# sensor.net
KiCad netlist of a schematic drawn in EAGLE
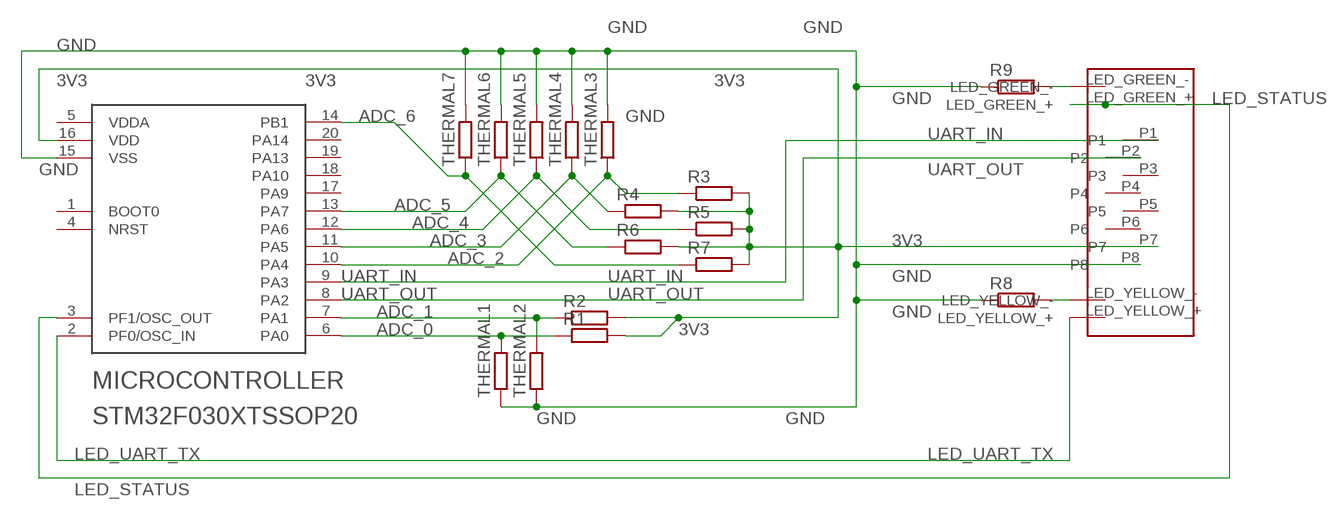
[diagram p0: schematic, sheet 1]

(export (version "E")
  (design (tool "Eeschema 10.0.6"))
  (components
    (comp (ref "MICROCONTROLLER")
      (value "STM32F030XTSSOP20")
      (footprint "eagle-import:TSSOP-20")
      (libsource (lib "eagle-import") (part "STM32F030XTSSOP20"))
    )
    (comp (ref "R1")
      (value "R-EU_0204/5")
      (footprint "eagle-import:0204_5")
      (libsource (lib "eagle-import") (part "R-EU_0204/5"))
    )
    (comp (ref "R2")
      (value "R-EU_0204/5")
      (footprint "eagle-import:0204_5")
      (libsource (lib "eagle-import") (part "R-EU_0204/5"))
    )
    (comp (ref "R3")
      (value "R-EU_0204/5")
      (footprint "eagle-import:0204_5")
      (libsource (lib "eagle-import") (part "R-EU_0204/5"))
    )
    (comp (ref "R4")
      (value "R-EU_0204/5")
      (footprint "eagle-import:0204_5")
      (libsource (lib "eagle-import") (part "R-EU_0204/5"))
    )
    (comp (ref "R5")
      (value "R-EU_0204/5")
      (footprint "eagle-import:0204_5")
      (libsource (lib "eagle-import") (part "R-EU_0204/5"))
    )
    (comp (ref "R6")
      (value "R-EU_0204/5")
      (footprint "eagle-import:0204_5")
      (libsource (lib "eagle-import") (part "R-EU_0204/5"))
    )
    (comp (ref "R7")
      (value "R-EU_0204/5")
      (footprint "eagle-import:0204_5")
      (libsource (lib "eagle-import") (part "R-EU_0204/5"))
    )
    (comp (ref "R8")
      (value "R-EU_0204/5")
      (footprint "eagle-import:0204_5")
      (libsource (lib "eagle-import") (part "R-EU_0204/5"))
    )
    (comp (ref "R9")
      (value "R-EU_0204/5")
      (footprint "eagle-import:0204_5")
      (libsource (lib "eagle-import") (part "R-EU_0204/5"))
    )
    (comp (ref "THERMAL1")
      (value "R-EU_V526-0")
      (footprint "eagle-import:V526-0")
      (libsource (lib "eagle-import") (part "R-EU_V526-0"))
    )
    (comp (ref "THERMAL2")
      (value "R-EU_V526-0")
      (footprint "eagle-import:V526-0")
      (libsource (lib "eagle-import") (part "R-EU_V526-0"))
    )
    (comp (ref "THERMAL3")
      (value "R-EU_V526-0")
      (footprint "eagle-import:V526-0")
      (libsource (lib "eagle-import") (part "R-EU_V526-0"))
    )
    (comp (ref "THERMAL4")
      (value "R-EU_V526-0")
      (footprint "eagle-import:V526-0")
      (libsource (lib "eagle-import") (part "R-EU_V526-0"))
    )
    (comp (ref "THERMAL5")
      (value "R-EU_V526-0")
      (footprint "eagle-import:V526-0")
      (libsource (lib "eagle-import") (part "R-EU_V526-0"))
    )
    (comp (ref "THERMAL6")
      (value "R-EU_V526-0")
      (footprint "eagle-import:V526-0")
      (libsource (lib "eagle-import") (part "R-EU_V526-0"))
    )
    (comp (ref "THERMAL7")
      (value "R-EU_V526-0")
      (footprint "eagle-import:V526-0")
      (libsource (lib "eagle-import") (part "R-EU_V526-0"))
    )
    (comp (ref "U$1")
      (value "RJHSE-5481_(RJ45)")
      (footprint "eagle-import:RJHSE-5481_(RJ45)")
      (libsource (lib "eagle-import") (part "RJHSE-5481_(RJ45)"))
    )
  )
  (nets
    (net (code "1") (name "/3V3") (class "Default")
      (node (ref "MICROCONTROLLER") (pin "16") (pinfunction "VDD_16") (pintype "bidirectional"))
      (node (ref "R1") (pin "2") (pinfunction "2_2") (pintype "passive"))
      (node (ref "R2") (pin "2") (pinfunction "2_2") (pintype "passive"))
      (node (ref "R3") (pin "2") (pinfunction "2_2") (pintype "passive"))
      (node (ref "R4") (pin "2") (pinfunction "2_2") (pintype "passive"))
      (node (ref "R5") (pin "2") (pinfunction "2_2") (pintype "passive"))
      (node (ref "R6") (pin "2") (pinfunction "2_2") (pintype "passive"))
      (node (ref "R7") (pin "2") (pinfunction "2_2") (pintype "passive"))
      (node (ref "U$1") (pin "P7") (pinfunction "P7_P7") (pintype "bidirectional"))
    )
    (net (code "2") (name "/ADC_0") (class "Default")
      (node (ref "MICROCONTROLLER") (pin "6") (pinfunction "PA0_6") (pintype "bidirectional"))
      (node (ref "R1") (pin "1") (pinfunction "1_1") (pintype "passive"))
      (node (ref "THERMAL1") (pin "2") (pinfunction "2_2") (pintype "passive"))
    )
    (net (code "3") (name "/ADC_1") (class "Default")
      (node (ref "MICROCONTROLLER") (pin "7") (pinfunction "PA1_7") (pintype "bidirectional"))
      (node (ref "R2") (pin "1") (pinfunction "1_1") (pintype "passive"))
      (node (ref "THERMAL2") (pin "2") (pinfunction "2_2") (pintype "passive"))
    )
    (net (code "4") (name "/ADC_2") (class "Default")
      (node (ref "MICROCONTROLLER") (pin "10") (pinfunction "PA4_10") (pintype "bidirectional"))
      (node (ref "R3") (pin "1") (pinfunction "1_1") (pintype "passive"))
      (node (ref "THERMAL3") (pin "1") (pinfunction "1_1") (pintype "passive"))
    )
    (net (code "5") (name "/ADC_3") (class "Default")
      (node (ref "MICROCONTROLLER") (pin "11") (pinfunction "PA5_11") (pintype "bidirectional"))
      (node (ref "R4") (pin "1") (pinfunction "1_1") (pintype "passive"))
      (node (ref "THERMAL4") (pin "1") (pinfunction "1_1") (pintype "passive"))
    )
    (net (code "6") (name "/ADC_4") (class "Default")
      (node (ref "MICROCONTROLLER") (pin "12") (pinfunction "PA6_12") (pintype "bidirectional"))
      (node (ref "R5") (pin "1") (pinfunction "1_1") (pintype "passive"))
      (node (ref "THERMAL5") (pin "1") (pinfunction "1_1") (pintype "passive"))
    )
    (net (code "7") (name "/ADC_5") (class "Default")
      (node (ref "MICROCONTROLLER") (pin "13") (pinfunction "PA7_13") (pintype "bidirectional"))
      (node (ref "R6") (pin "1") (pinfunction "1_1") (pintype "passive"))
      (node (ref "THERMAL6") (pin "1") (pinfunction "1_1") (pintype "passive"))
    )
    (net (code "8") (name "/ADC_6") (class "Default")
      (node (ref "MICROCONTROLLER") (pin "14") (pinfunction "PB1_14") (pintype "bidirectional"))
      (node (ref "R7") (pin "1") (pinfunction "1_1") (pintype "passive"))
      (node (ref "THERMAL7") (pin "1") (pinfunction "1_1") (pintype "passive"))
    )
    (net (code "9") (name "/GND") (class "Default")
      (node (ref "MICROCONTROLLER") (pin "15") (pinfunction "VSS_15") (pintype "bidirectional"))
      (node (ref "R8") (pin "1") (pinfunction "1_1") (pintype "passive"))
      (node (ref "R9") (pin "1") (pinfunction "1_1") (pintype "passive"))
      (node (ref "THERMAL1") (pin "1") (pinfunction "1_1") (pintype "passive"))
      (node (ref "THERMAL2") (pin "1") (pinfunction "1_1") (pintype "passive"))
      (node (ref "THERMAL3") (pin "2") (pinfunction "2_2") (pintype "passive"))
      (node (ref "THERMAL4") (pin "2") (pinfunction "2_2") (pintype "passive"))
      (node (ref "THERMAL5") (pin "2") (pinfunction "2_2") (pintype "passive"))
      (node (ref "THERMAL6") (pin "2") (pinfunction "2_2") (pintype "passive"))
      (node (ref "THERMAL7") (pin "2") (pinfunction "2_2") (pintype "passive"))
      (node (ref "U$1") (pin "P8") (pinfunction "P8_P8") (pintype "bidirectional"))
    )
    (net (code "10") (name "/LED_STATUS") (class "Default")
      (node (ref "MICROCONTROLLER") (pin "3") (pinfunction "PF1/OSC_OUT_3") (pintype "bidirectional"))
      (node (ref "U$1") (pin "LED_GREEN_+") (pinfunction "LED_GREEN_+_LED_GREEN_+") (pintype "input"))
    )
    (net (code "11") (name "/LED_UART_TX") (class "Default")
      (node (ref "MICROCONTROLLER") (pin "2") (pinfunction "PF0/OSC_IN_2") (pintype "bidirectional"))
    )
    (net (code "12") (name "/UART_IN") (class "Default")
      (node (ref "MICROCONTROLLER") (pin "9") (pinfunction "PA3_9") (pintype "bidirectional"))
      (node (ref "U$1") (pin "P1") (pinfunction "P1_P1") (pintype "bidirectional"))
    )
    (net (code "13") (name "/UART_OUT") (class "Default")
      (node (ref "MICROCONTROLLER") (pin "8") (pinfunction "PA2_8") (pintype "bidirectional"))
      (node (ref "U$1") (pin "P2") (pinfunction "P2_P2") (pintype "bidirectional"))
    )
    (net (code "14") (name "unconnected-(MICROCONTROLLER-BOOT0-Pad1)") (class "Default")
      (node (ref "MICROCONTROLLER") (pin "1") (pinfunction "BOOT0_1") (pintype "bidirectional"))
    )
    (net (code "15") (name "unconnected-(MICROCONTROLLER-NRST-Pad4)") (class "Default")
      (node (ref "MICROCONTROLLER") (pin "4") (pinfunction "NRST_4") (pintype "bidirectional"))
    )
    (net (code "16") (name "unconnected-(MICROCONTROLLER-PA9-Pad17)") (class "Default")
      (node (ref "MICROCONTROLLER") (pin "17") (pinfunction "PA9_17") (pintype "bidirectional"))
    )
    (net (code "17") (name "unconnected-(MICROCONTROLLER-PA10-Pad18)") (class "Default")
      (node (ref "MICROCONTROLLER") (pin "18") (pinfunction "PA10_18") (pintype "bidirectional"))
    )
    (net (code "18") (name "unconnected-(MICROCONTROLLER-PA13-Pad19)") (class "Default")
      (node (ref "MICROCONTROLLER") (pin "19") (pinfunction "PA13_19") (pintype "bidirectional"))
    )
    (net (code "19") (name "unconnected-(MICROCONTROLLER-PA14-Pad20)") (class "Default")
      (node (ref "MICROCONTROLLER") (pin "20") (pinfunction "PA14_20") (pintype "bidirectional"))
    )
    (net (code "20") (name "unconnected-(MICROCONTROLLER-VDDA-Pad5)") (class "Default")
      (node (ref "MICROCONTROLLER") (pin "5") (pinfunction "VDDA_5") (pintype "bidirectional"))
    )
    (net (code "21") (name "unconnected-(R8-Pad2)") (class "Default")
      (node (ref "R8") (pin "2") (pinfunction "2_2") (pintype "passive"))
    )
    (net (code "22") (name "unconnected-(R9-Pad2)") (class "Default")
      (node (ref "R9") (pin "2") (pinfunction "2_2") (pintype "passive"))
    )
    (net (code "23") (name "unconnected-(U$1-PadLED_GREEN_-)") (class "Default")
      (node (ref "U$1") (pin "LED_GREEN_-") (pinfunction "LED_GREEN_-_LED_GREEN_-") (pintype "input"))
    )
    (net (code "24") (name "unconnected-(U$1-PadLED_YELLOW_+)") (class "Default")
      (node (ref "U$1") (pin "LED_YELLOW_+") (pinfunction "LED_YELLOW_+_LED_YELLOW_+") (pintype "input"))
    )
    (net (code "25") (name "unconnected-(U$1-PadLED_YELLOW_-)") (class "Default")
      (node (ref "U$1") (pin "LED_YELLOW_-") (pinfunction "LED_YELLOW_-_LED_YELLOW_-") (pintype "input"))
    )
    (net (code "26") (name "unconnected-(U$1-PadP3)") (class "Default")
      (node (ref "U$1") (pin "P3") (pinfunction "P3_P3") (pintype "bidirectional"))
    )
    (net (code "27") (name "unconnected-(U$1-PadP4)") (class "Default")
      (node (ref "U$1") (pin "P4") (pinfunction "P4_P4") (pintype "bidirectional"))
    )
    (net (code "28") (name "unconnected-(U$1-PadP5)") (class "Default")
      (node (ref "U$1") (pin "P5") (pinfunction "P5_P5") (pintype "bidirectional"))
    )
    (net (code "29") (name "unconnected-(U$1-PadP6)") (class "Default")
      (node (ref "U$1") (pin "P6") (pinfunction "P6_P6") (pintype "bidirectional"))
    )
  )
)
